# ThunderBolt_Nova_Pico.net
KiCad netlist of a schematic drawn in EAGLE
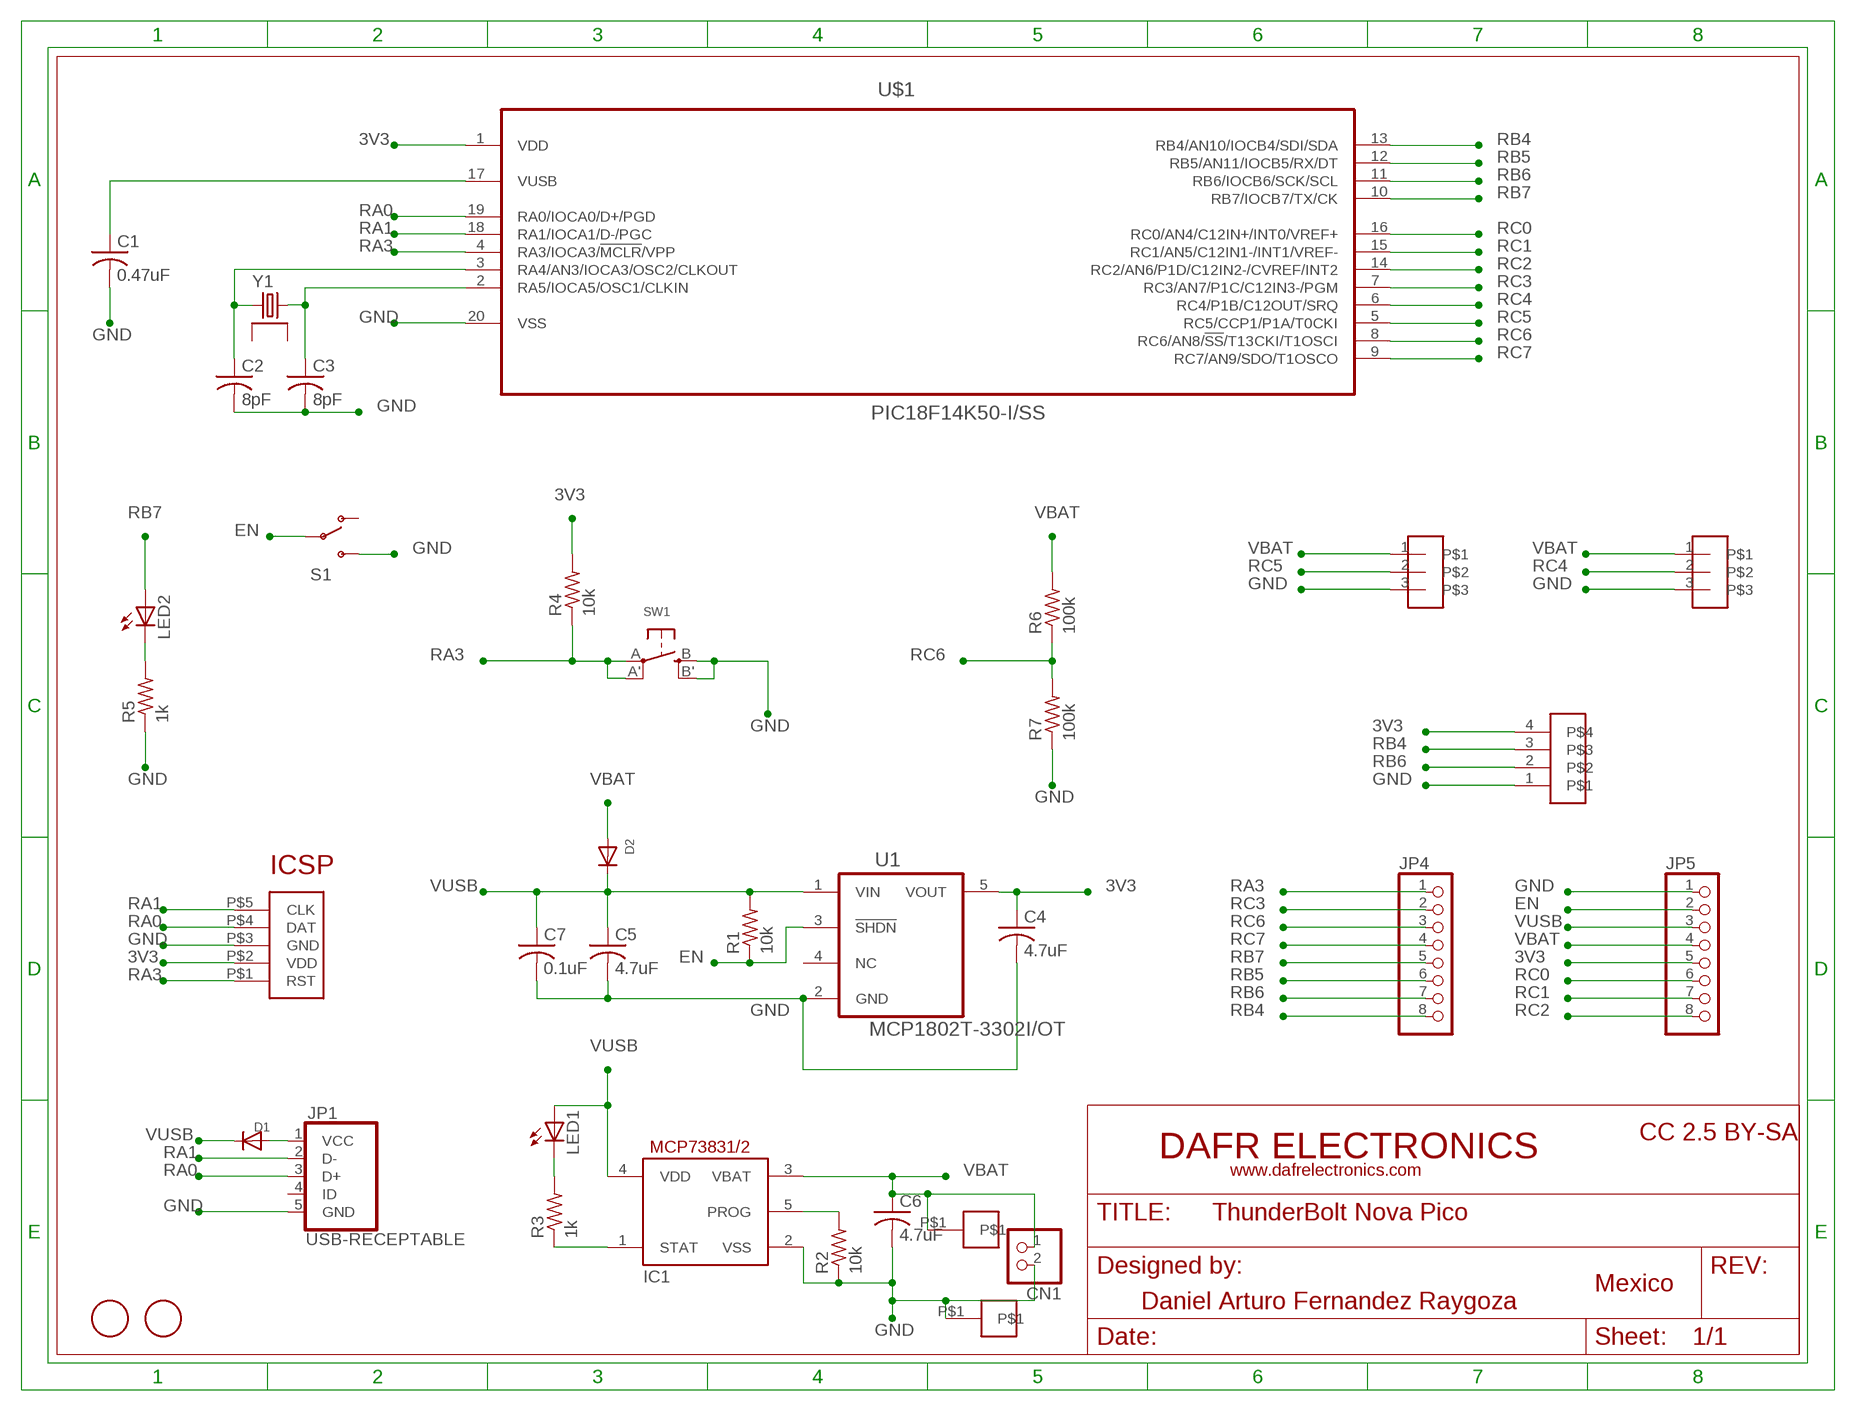
[diagram p0: schematic, sheet 1]

(export (version "E")
  (design (tool "Eeschema 10.0.6"))
  (components
    (comp (ref "C1")
      (value "0.47uF")
      (footprint "eagle-import:C0805K")
      (libsource (lib "eagle-import") (part "C-USC0805K"))
    )
    (comp (ref "C2")
      (value "8pF")
      (footprint "eagle-import:C0805K")
      (libsource (lib "eagle-import") (part "C-USC0805K"))
    )
    (comp (ref "C3")
      (value "8pF")
      (footprint "eagle-import:C0805K")
      (libsource (lib "eagle-import") (part "C-USC0805K"))
    )
    (comp (ref "C4")
      (value "4.7uF")
      (footprint "eagle-import:C0805K")
      (libsource (lib "eagle-import") (part "C-USC0805K"))
    )
    (comp (ref "C5")
      (value "4.7uF")
      (footprint "eagle-import:C0805K")
      (libsource (lib "eagle-import") (part "C-USC0805K"))
    )
    (comp (ref "C6")
      (value "4.7uF")
      (footprint "eagle-import:C0805K")
      (libsource (lib "eagle-import") (part "C-USC0805K"))
    )
    (comp (ref "C7")
      (value "0.1uF")
      (footprint "eagle-import:C0603K")
      (libsource (lib "eagle-import") (part "C-USC0603K"))
    )
    (comp (ref "CN1")
      (value "JST_2PIN-SMT-RA")
      (footprint "eagle-import:JST-PH-2-SMT-RA")
      (libsource (lib "eagle-import") (part "JST_2PIN-SMT-RA"))
    )
    (comp (ref "D1")
      (value "DIODESOD-123")
      (footprint "eagle-import:SOD-123")
      (libsource (lib "eagle-import") (part "DIODESOD-123"))
    )
    (comp (ref "D2")
      (value "DIODESOD-123")
      (footprint "eagle-import:SOD-123")
      (libsource (lib "eagle-import") (part "DIODESOD-123"))
    )
    (comp (ref "IC1")
      (value "MCP73831/OT")
      (footprint "eagle-import:SOT23-5L")
      (libsource (lib "eagle-import") (part "MCP73831/OT"))
    )
    (comp (ref "JP1")
      (value "USB-RECEPTABLE")
      (footprint "eagle-import:FCI-10103594-0001LF")
      (libsource (lib "eagle-import") (part "USB-RECEPTABLE"))
    )
    (comp (ref "JP4")
      (value "PINHD-1X8BIG")
      (footprint "eagle-import:1X08-BIG")
      (libsource (lib "eagle-import") (part "PINHD-1X8BIG"))
    )
    (comp (ref "JP5")
      (value "PINHD-1X8BIG")
      (footprint "eagle-import:1X08-BIG")
      (libsource (lib "eagle-import") (part "PINHD-1X8BIG"))
    )
    (comp (ref "LED1")
      (value "LEDCHIPLED_1206")
      (footprint "eagle-import:CHIPLED_1206")
      (libsource (lib "eagle-import") (part "LEDCHIPLED_1206"))
    )
    (comp (ref "LED2")
      (value "LEDCHIPLED_1206")
      (footprint "eagle-import:CHIPLED_1206")
      (libsource (lib "eagle-import") (part "LEDCHIPLED_1206"))
    )
    (comp (ref "R1")
      (value "10k")
      (footprint "eagle-import:R0805")
      (libsource (lib "eagle-import") (part "R-US_R0805"))
    )
    (comp (ref "R2")
      (value "10k")
      (footprint "eagle-import:R0805")
      (libsource (lib "eagle-import") (part "R-US_R0805"))
    )
    (comp (ref "R3")
      (value "1k")
      (footprint "eagle-import:R0805")
      (libsource (lib "eagle-import") (part "R-US_R0805"))
    )
    (comp (ref "R4")
      (value "10k")
      (footprint "eagle-import:R0805")
      (libsource (lib "eagle-import") (part "R-US_R0805"))
    )
    (comp (ref "R5")
      (value "1k")
      (footprint "eagle-import:R0805")
      (libsource (lib "eagle-import") (part "R-US_R0805"))
    )
    (comp (ref "R6")
      (value "100k")
      (footprint "eagle-import:R0805")
      (libsource (lib "eagle-import") (part "R-US_R0805"))
    )
    (comp (ref "R7")
      (value "100k")
      (footprint "eagle-import:R0805")
      (libsource (lib "eagle-import") (part "R-US_R0805"))
    )
    (comp (ref "S1")
      (value "SWITCH-SPDT-SMD-A")
      (footprint "eagle-import:SWITCH-SPST-SMD-A")
      (libsource (lib "eagle-import") (part "SWITCH-SPDT-SMD-A"))
    )
    (comp (ref "SW1")
      (value "SWITCH_TACT_SMT4.6X2.8")
      (footprint "eagle-import:BTN_KMR2_4.6X2.8")
      (libsource (lib "eagle-import") (part "SWITCH_TACT_SMT4.6X2.8"))
    )
    (comp (ref "U$1")
      (value "PIC18F14K50-I/SS")
      (footprint "eagle-import:SOP65P780X200-20N")
      (libsource (lib "eagle-import") (part "PIC18F14K50-I/SS"))
    )
    (comp (ref "U$2")
      (value "ICSP_POGO")
      (footprint "eagle-import:ICSP_POGO")
      (libsource (lib "eagle-import") (part "ICSP_POGO"))
    )
    (comp (ref "U$3")
      (value "PADSMD")
      (footprint "eagle-import:PADSMD")
      (libsource (lib "eagle-import") (part "PADSMD"))
    )
    (comp (ref "U$4")
      (value "PADSMD")
      (footprint "eagle-import:PADSMD")
      (libsource (lib "eagle-import") (part "PADSMD"))
    )
    (comp (ref "U$5")
      (value "PIN1X3")
      (footprint "eagle-import:PIN1X3")
      (libsource (lib "eagle-import") (part "PIN1X3"))
    )
    (comp (ref "U$6")
      (value "PIN1X3")
      (footprint "eagle-import:PIN1X3")
      (libsource (lib "eagle-import") (part "PIN1X3"))
    )
    (comp (ref "U$7")
      (value "PIN1X4")
      (footprint "eagle-import:PIN1X4")
      (libsource (lib "eagle-import") (part "PIN1X4"))
    )
    (comp (ref "U$8")
      (value "FIDUCIAL")
      (footprint "eagle-import:FIDUCIAL_1MM")
      (libsource (lib "eagle-import") (part "FIDUCIAL"))
    )
    (comp (ref "U$9")
      (value "FIDUCIAL")
      (footprint "eagle-import:FIDUCIAL_1MM")
      (libsource (lib "eagle-import") (part "FIDUCIAL"))
    )
    (comp (ref "U1")
      (value "MCP1802T-3302I/OT")
      (footprint "eagle-import:SOT95P270X145-5N")
      (libsource (lib "eagle-import") (part "MCP1802T-3302I/OT"))
    )
    (comp (ref "Y1")
      (value "GRX-330")
      (footprint "eagle-import:OSC3225")
      (libsource (lib "eagle-import") (part "GRX-330"))
    )
  )
  (nets
    (net (code "1") (name "/3V3") (class "Default")
      (node (ref "C4") (pin "1") (pinfunction "1_1") (pintype "passive"))
      (node (ref "JP5") (pin "5") (pinfunction "5_5") (pintype "passive"))
      (node (ref "R4") (pin "2") (pinfunction "2_2") (pintype "passive"))
      (node (ref "U$1") (pin "1") (pinfunction "VDD_1") (pintype "power_in"))
      (node (ref "U$2") (pin "P$2") (pinfunction "VDD_P$2") (pintype "bidirectional"))
      (node (ref "U$7") (pin "4") (pinfunction "P$4_4") (pintype "bidirectional"))
      (node (ref "U1") (pin "5") (pinfunction "VOUT_5") (pintype "output"))
    )
    (net (code "2") (name "/EN") (class "Default")
      (node (ref "JP5") (pin "2") (pinfunction "2_2") (pintype "passive"))
      (node (ref "R1") (pin "1") (pinfunction "1_1") (pintype "passive"))
      (node (ref "S1") (pin "2") (pinfunction "P_2") (pintype "passive"))
      (node (ref "U1") (pin "3") (pinfunction "~{SHDN}_3") (pintype "input"))
    )
    (net (code "3") (name "/GND") (class "Default")
      (node (ref "C1") (pin "2") (pinfunction "2_2") (pintype "passive"))
      (node (ref "C2") (pin "2") (pinfunction "2_2") (pintype "passive"))
      (node (ref "C3") (pin "2") (pinfunction "2_2") (pintype "passive"))
      (node (ref "C4") (pin "2") (pinfunction "2_2") (pintype "passive"))
      (node (ref "C5") (pin "2") (pinfunction "2_2") (pintype "passive"))
      (node (ref "C6") (pin "2") (pinfunction "2_2") (pintype "passive"))
      (node (ref "C7") (pin "2") (pinfunction "2_2") (pintype "passive"))
      (node (ref "CN1") (pin "2") (pinfunction "1_2") (pintype "passive"))
      (node (ref "IC1") (pin "2") (pinfunction "VSS_2") (pintype "power_in"))
      (node (ref "JP1") (pin "5") (pinfunction "GND_5") (pintype "bidirectional"))
      (node (ref "JP5") (pin "1") (pinfunction "1_1") (pintype "passive"))
      (node (ref "R2") (pin "1") (pinfunction "1_1") (pintype "passive"))
      (node (ref "R5") (pin "1") (pinfunction "1_1") (pintype "passive"))
      (node (ref "R7") (pin "1") (pinfunction "1_1") (pintype "passive"))
      (node (ref "S1") (pin "3") (pinfunction "S_3") (pintype "passive"))
      (node (ref "SW1") (pin "B") (pinfunction "S_B") (pintype "passive"))
      (node (ref "SW1") (pin "B'") (pinfunction "S1_B'") (pintype "passive"))
      (node (ref "U$1") (pin "20") (pinfunction "VSS_20") (pintype "passive"))
      (node (ref "U$2") (pin "P$3") (pinfunction "GND_P$3") (pintype "bidirectional"))
      (node (ref "U$3") (pin "P$1") (pinfunction "P$1_P$1") (pintype "bidirectional"))
      (node (ref "U$5") (pin "3") (pinfunction "P$3_3") (pintype "bidirectional"))
      (node (ref "U$6") (pin "3") (pinfunction "P$3_3") (pintype "bidirectional"))
      (node (ref "U$7") (pin "1") (pinfunction "P$1_1") (pintype "bidirectional"))
      (node (ref "U1") (pin "2") (pinfunction "GND_2") (pintype "passive"))
    )
    (net (code "4") (name "/RA0") (class "Default")
      (node (ref "JP1") (pin "3") (pinfunction "D+_3") (pintype "bidirectional"))
      (node (ref "U$1") (pin "19") (pinfunction "RA0/IOCA0/D+/PGD_19") (pintype "bidirectional"))
      (node (ref "U$2") (pin "P$4") (pinfunction "DAT_P$4") (pintype "bidirectional"))
    )
    (net (code "5") (name "/RA1") (class "Default")
      (node (ref "JP1") (pin "2") (pinfunction "D-_2") (pintype "bidirectional"))
      (node (ref "U$1") (pin "18") (pinfunction "RA1/IOCA1/D-/PGC_18") (pintype "bidirectional"))
      (node (ref "U$2") (pin "P$5") (pinfunction "CLK_P$5") (pintype "bidirectional"))
    )
    (net (code "6") (name "/RA3") (class "Default")
      (node (ref "JP4") (pin "1") (pinfunction "1_1") (pintype "passive"))
      (node (ref "R4") (pin "1") (pinfunction "1_1") (pintype "passive"))
      (node (ref "SW1") (pin "A") (pinfunction "P_A") (pintype "passive"))
      (node (ref "SW1") (pin "A'") (pinfunction "P1_A'") (pintype "passive"))
      (node (ref "U$1") (pin "4") (pinfunction "RA3/IOCA3/~{MCLR}/VPP_4") (pintype "bidirectional"))
      (node (ref "U$2") (pin "P$1") (pinfunction "RST_P$1") (pintype "bidirectional"))
    )
    (net (code "7") (name "/RB4") (class "Default")
      (node (ref "JP4") (pin "8") (pinfunction "8_8") (pintype "passive"))
      (node (ref "U$1") (pin "13") (pinfunction "RB4/AN10/IOCB4/SDI/SDA_13") (pintype "bidirectional"))
      (node (ref "U$7") (pin "3") (pinfunction "P$3_3") (pintype "bidirectional"))
    )
    (net (code "8") (name "/RB5") (class "Default")
      (node (ref "JP4") (pin "6") (pinfunction "6_6") (pintype "passive"))
      (node (ref "U$1") (pin "12") (pinfunction "RB5/AN11/IOCB5/RX/DT_12") (pintype "bidirectional"))
    )
    (net (code "9") (name "/RB6") (class "Default")
      (node (ref "JP4") (pin "7") (pinfunction "7_7") (pintype "passive"))
      (node (ref "U$1") (pin "11") (pinfunction "RB6/IOCB6/SCK/SCL_11") (pintype "bidirectional"))
      (node (ref "U$7") (pin "2") (pinfunction "P$2_2") (pintype "bidirectional"))
    )
    (net (code "10") (name "/RB7") (class "Default")
      (node (ref "JP4") (pin "5") (pinfunction "5_5") (pintype "passive"))
      (node (ref "LED2") (pin "A") (pinfunction "A_A") (pintype "passive"))
      (node (ref "U$1") (pin "10") (pinfunction "RB7/IOCB7/TX/CK_10") (pintype "bidirectional"))
    )
    (net (code "11") (name "/RC0") (class "Default")
      (node (ref "JP5") (pin "6") (pinfunction "6_6") (pintype "passive"))
      (node (ref "U$1") (pin "16") (pinfunction "RC0/AN4/C12IN+/INT0/VREF+_16") (pintype "power_in"))
    )
    (net (code "12") (name "/RC1") (class "Default")
      (node (ref "JP5") (pin "7") (pinfunction "7_7") (pintype "passive"))
      (node (ref "U$1") (pin "15") (pinfunction "RC1/AN5/C12IN1-/INT1/VREF-_15") (pintype "power_in"))
    )
    (net (code "13") (name "/RC2") (class "Default")
      (node (ref "JP5") (pin "8") (pinfunction "8_8") (pintype "passive"))
      (node (ref "U$1") (pin "14") (pinfunction "RC2/AN6/P1D/C12IN2-/CVREF/INT2_14") (pintype "bidirectional"))
    )
    (net (code "14") (name "/RC3") (class "Default")
      (node (ref "JP4") (pin "2") (pinfunction "2_2") (pintype "passive"))
      (node (ref "U$1") (pin "7") (pinfunction "RC3/AN7/P1C/C12IN3-/PGM_7") (pintype "bidirectional"))
    )
    (net (code "15") (name "/RC4") (class "Default")
      (node (ref "U$1") (pin "6") (pinfunction "RC4/P1B/C12OUT/SRQ_6") (pintype "bidirectional"))
      (node (ref "U$5") (pin "2") (pinfunction "P$2_2") (pintype "bidirectional"))
    )
    (net (code "16") (name "/RC5") (class "Default")
      (node (ref "U$1") (pin "5") (pinfunction "RC5/CCP1/P1A/T0CKI_5") (pintype "bidirectional"))
      (node (ref "U$6") (pin "2") (pinfunction "P$2_2") (pintype "bidirectional"))
    )
    (net (code "17") (name "/RC6") (class "Default")
      (node (ref "JP4") (pin "3") (pinfunction "3_3") (pintype "passive"))
      (node (ref "R6") (pin "1") (pinfunction "1_1") (pintype "passive"))
      (node (ref "R7") (pin "2") (pinfunction "2_2") (pintype "passive"))
      (node (ref "U$1") (pin "8") (pinfunction "RC6/AN8/~{SS}/T13CKI/T1OSCI_8") (pintype "bidirectional"))
    )
    (net (code "18") (name "/RC7") (class "Default")
      (node (ref "JP4") (pin "4") (pinfunction "4_4") (pintype "passive"))
      (node (ref "U$1") (pin "9") (pinfunction "RC7/AN9/SDO/T1OSCO_9") (pintype "bidirectional"))
    )
    (net (code "19") (name "/VBAT") (class "Default")
      (node (ref "C6") (pin "1") (pinfunction "1_1") (pintype "passive"))
      (node (ref "CN1") (pin "1") (pinfunction "2_1") (pintype "passive"))
      (node (ref "D2") (pin "A") (pinfunction "A_A") (pintype "passive"))
      (node (ref "IC1") (pin "3") (pinfunction "VBAT_3") (pintype "bidirectional"))
      (node (ref "JP5") (pin "4") (pinfunction "4_4") (pintype "passive"))
      (node (ref "R6") (pin "2") (pinfunction "2_2") (pintype "passive"))
      (node (ref "U$4") (pin "P$1") (pinfunction "P$1_P$1") (pintype "bidirectional"))
      (node (ref "U$5") (pin "1") (pinfunction "P$1_1") (pintype "bidirectional"))
      (node (ref "U$6") (pin "1") (pinfunction "P$1_1") (pintype "bidirectional"))
    )
    (net (code "20") (name "/VUSB") (class "Default")
      (node (ref "C5") (pin "1") (pinfunction "1_1") (pintype "passive"))
      (node (ref "C7") (pin "1") (pinfunction "1_1") (pintype "passive"))
      (node (ref "D1") (pin "C") (pinfunction "C_C") (pintype "passive"))
      (node (ref "D2") (pin "C") (pinfunction "C_C") (pintype "passive"))
      (node (ref "IC1") (pin "4") (pinfunction "VDD_4") (pintype "power_in"))
      (node (ref "JP5") (pin "3") (pinfunction "3_3") (pintype "passive"))
      (node (ref "LED1") (pin "A") (pinfunction "A_A") (pintype "passive"))
      (node (ref "R1") (pin "2") (pinfunction "2_2") (pintype "passive"))
      (node (ref "U1") (pin "1") (pinfunction "VIN_1") (pintype "power_in"))
    )
    (net (code "21") (name "Net-(IC1-PROG)") (class "Default")
      (node (ref "IC1") (pin "5") (pinfunction "PROG_5") (pintype "input"))
      (node (ref "R2") (pin "2") (pinfunction "2_2") (pintype "passive"))
    )
    (net (code "22") (name "Net-(IC1-STAT)") (class "Default")
      (node (ref "IC1") (pin "1") (pinfunction "STAT_1") (pintype "output"))
      (node (ref "R3") (pin "1") (pinfunction "1_1") (pintype "passive"))
    )
    (net (code "23") (name "Net-(JP1-VCC)") (class "Default")
      (node (ref "D1") (pin "A") (pinfunction "A_A") (pintype "passive"))
      (node (ref "JP1") (pin "1") (pinfunction "VCC_1") (pintype "bidirectional"))
    )
    (net (code "24") (name "Net-(LED1-PadC)") (class "Default")
      (node (ref "LED1") (pin "C") (pinfunction "C_C") (pintype "passive"))
      (node (ref "R3") (pin "2") (pinfunction "2_2") (pintype "passive"))
    )
    (net (code "25") (name "Net-(LED2-PadC)") (class "Default")
      (node (ref "LED2") (pin "C") (pinfunction "C_C") (pintype "passive"))
      (node (ref "R5") (pin "2") (pinfunction "2_2") (pintype "passive"))
    )
    (net (code "26") (name "Net-(U$1-RA4{slash}AN3{slash}IOCA3{slash}OSC2{slash}CLKOUT)") (class "Default")
      (node (ref "C2") (pin "1") (pinfunction "1_1") (pintype "passive"))
      (node (ref "U$1") (pin "3") (pinfunction "RA4/AN3/IOCA3/OSC2/CLKOUT_3") (pintype "input"))
      (node (ref "Y1") (pin "P$1") (pinfunction "1_P$1") (pintype "passive"))
    )
    (net (code "27") (name "Net-(U$1-RA5{slash}IOCA5{slash}OSC1{slash}CLKIN)") (class "Default")
      (node (ref "C3") (pin "1") (pinfunction "1_1") (pintype "passive"))
      (node (ref "U$1") (pin "2") (pinfunction "RA5/IOCA5/OSC1/CLKIN_2") (pintype "bidirectional"))
      (node (ref "Y1") (pin "P$3") (pinfunction "3_P$3") (pintype "passive"))
    )
    (net (code "28") (name "Net-(U$1-VUSB)") (class "Default")
      (node (ref "C1") (pin "1") (pinfunction "1_1") (pintype "passive"))
      (node (ref "U$1") (pin "17") (pinfunction "VUSB_17") (pintype "input"))
    )
    (net (code "29") (name "unconnected-(JP1-ID-Pad4)") (class "Default")
      (node (ref "JP1") (pin "4") (pinfunction "ID_4") (pintype "bidirectional"))
    )
    (net (code "30") (name "unconnected-(S1-O-Pad1)") (class "Default")
      (node (ref "S1") (pin "1") (pinfunction "O_1") (pintype "passive"))
    )
    (net (code "31") (name "unconnected-(U1-NC-Pad4)") (class "Default")
      (node (ref "U1") (pin "4") (pinfunction "NC_4") (pintype "no_connect"))
    )
    (net (code "32") (name "unconnected-(Y1-2-PadP$2)") (class "Default")
      (node (ref "Y1") (pin "P$2") (pinfunction "2_P$2") (pintype "passive"))
    )
    (net (code "33") (name "unconnected-(Y1-4-PadP$4)") (class "Default")
      (node (ref "Y1") (pin "P$4") (pinfunction "4_P$4") (pintype "passive"))
    )
  )
)
